# picoAvaR7.net
KiCad netlist of a schematic drawn in EAGLE
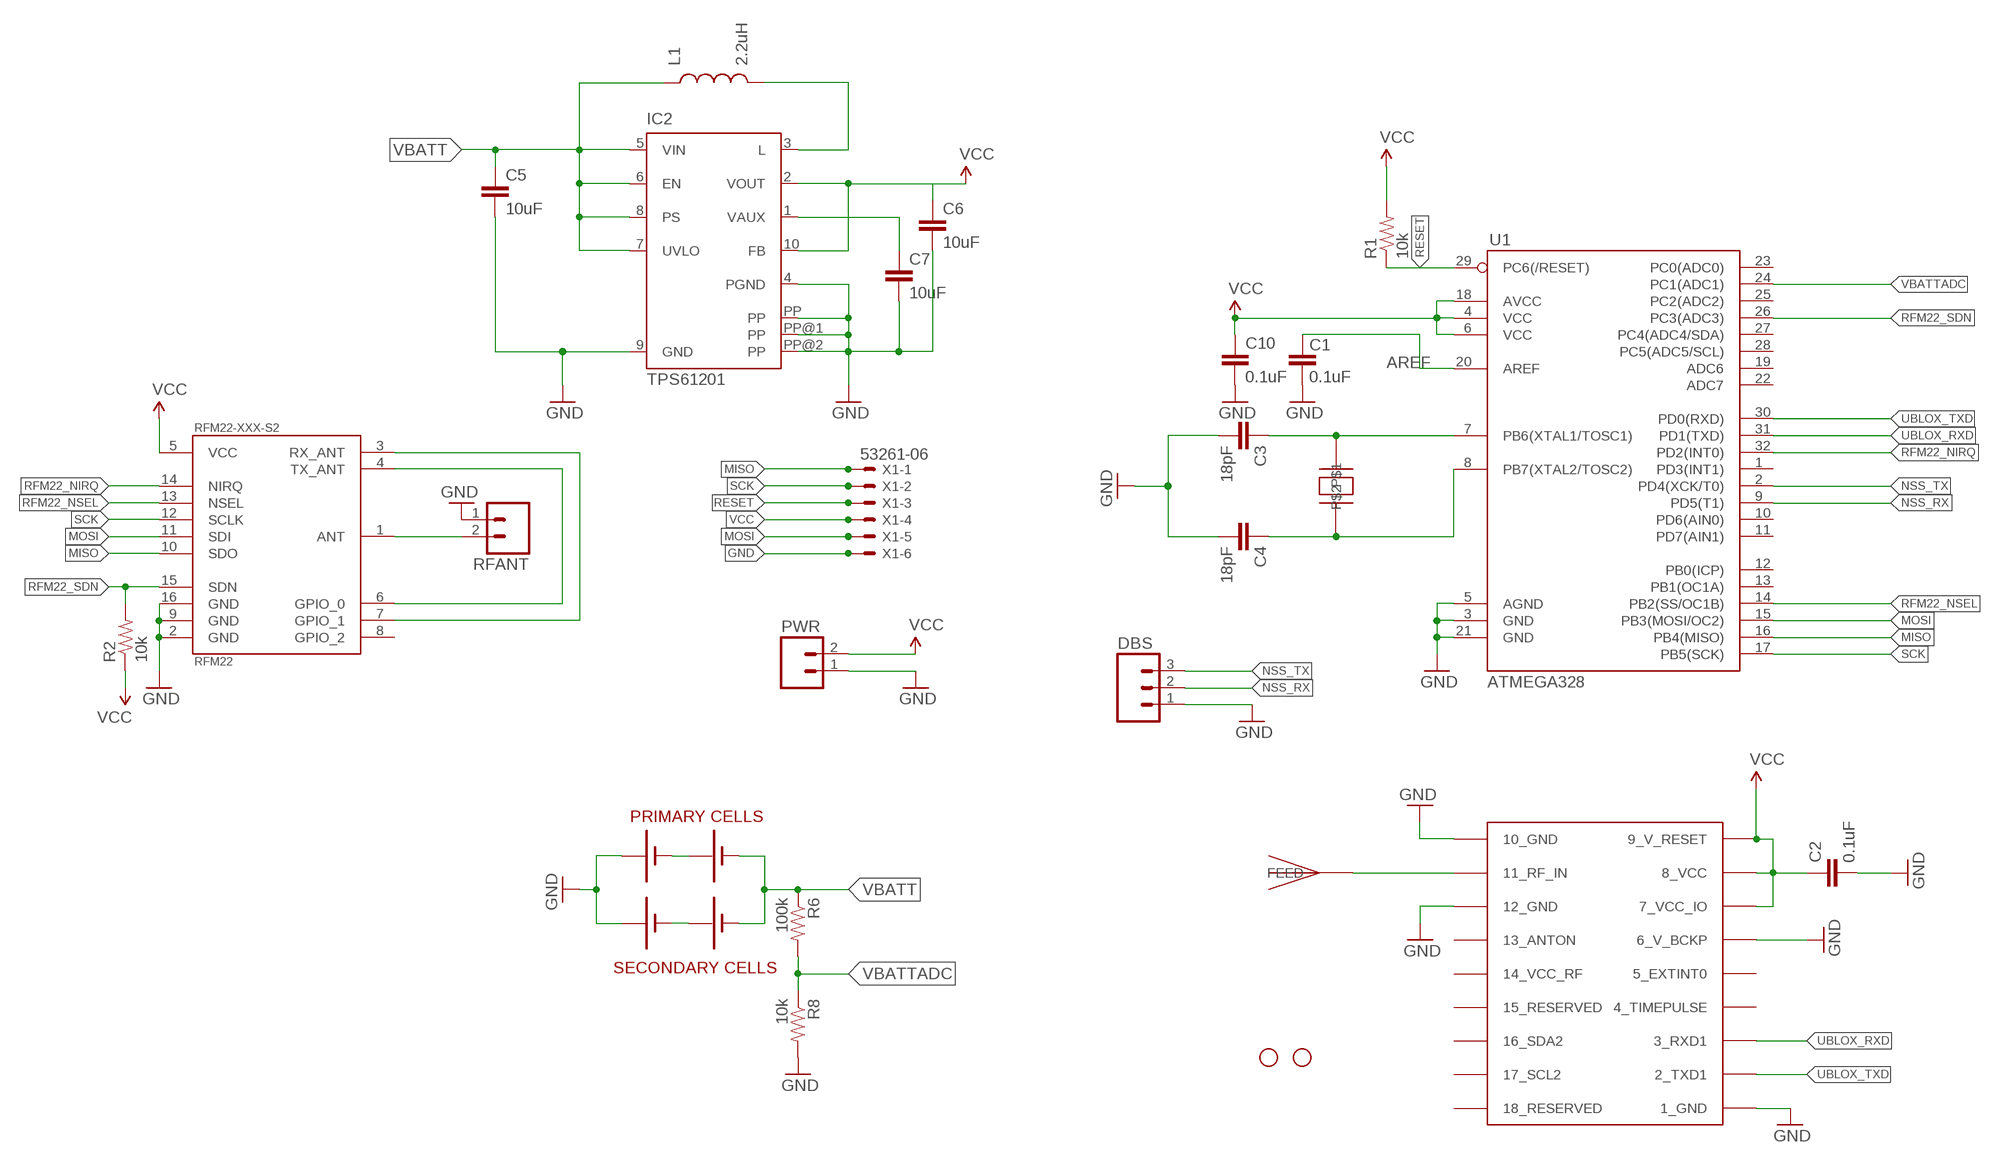
[diagram p0: schematic, sheet 1]

(export (version "E")
  (design (tool "Eeschema 10.0.6"))
  (components
    (comp (ref "C1")
      (value "0.1uF")
      (footprint "eagle-import:0402-CAP")
      (libsource (lib "eagle-import") (part "CAP0402-CAP"))
    )
    (comp (ref "C2")
      (value "0.1uF")
      (footprint "eagle-import:0402-CAP")
      (libsource (lib "eagle-import") (part "CAP0402-CAP"))
    )
    (comp (ref "C3")
      (value "18pF")
      (footprint "eagle-import:0402-CAP")
      (libsource (lib "eagle-import") (part "CAP0402-CAP"))
    )
    (comp (ref "C4")
      (value "18pF")
      (footprint "eagle-import:0402-CAP")
      (libsource (lib "eagle-import") (part "CAP0402-CAP"))
    )
    (comp (ref "C5")
      (value "10uF")
      (footprint "eagle-import:1206")
      (libsource (lib "eagle-import") (part "CAP1206"))
    )
    (comp (ref "C6")
      (value "10uF")
      (footprint "eagle-import:1206")
      (libsource (lib "eagle-import") (part "CAP1206"))
    )
    (comp (ref "C7")
      (value "10uF")
      (footprint "eagle-import:1206")
      (libsource (lib "eagle-import") (part "CAP1206"))
    )
    (comp (ref "C10")
      (value "0.1uF")
      (footprint "eagle-import:0402-CAP")
      (libsource (lib "eagle-import") (part "CAP0402-CAP"))
    )
    (comp (ref "DBS")
      (value "M03PTH")
      (footprint "eagle-import:1X03")
      (libsource (lib "eagle-import") (part "M03PTH"))
    )
    (comp (ref "IC2")
      (value "TPS61201")
      (footprint "eagle-import:S-PDSO-N10")
      (fields (field (name "MPN") "TPS61201DRCT"))
      (libsource (lib "eagle-import") (part "TPS61201"))
    )
    (comp (ref "JP1")
      (value "STAND-OFF")
      (footprint "eagle-import:STAND-OFF")
      (libsource (lib "eagle-import") (part "STAND-OFF"))
    )
    (comp (ref "JP2")
      (value "STAND-OFF")
      (footprint "eagle-import:STAND-OFF")
      (libsource (lib "eagle-import") (part "STAND-OFF"))
    )
    (comp (ref "L1")
      (value "2.2uH")
      (footprint "eagle-import:ELLVGG_INDUCTOR")
      (libsource (lib "eagle-import") (part "ELLVGG_INDUCTOR"))
    )
    (comp (ref "PRIMARYCELL1")
      (value "KEYSTONE-82-AAA-BATTERY-HOLDER")
      (footprint "eagle-import:KEYSTONE-82-AAA-BATTERY")
      (libsource (lib "eagle-import") (part "KEYSTONE-82-AAA-BATTERY-HOLDER"))
    )
    (comp (ref "PRIMARYCELL2")
      (value "KEYSTONE-82-AAA-BATTERY-HOLDER")
      (footprint "eagle-import:KEYSTONE-82-AAA-BATTERY")
      (libsource (lib "eagle-import") (part "KEYSTONE-82-AAA-BATTERY-HOLDER"))
    )
    (comp (ref "PWR")
      (value "M02PTH")
      (footprint "eagle-import:1X02")
      (libsource (lib "eagle-import") (part "M02PTH"))
    )
    (comp (ref "R1")
      (value "10k")
      (footprint "eagle-import:0402-RES")
      (libsource (lib "eagle-import") (part "RESISTOR0402-RES"))
    )
    (comp (ref "R2")
      (value "10k")
      (footprint "eagle-import:0402-RES")
      (libsource (lib "eagle-import") (part "RESISTOR0402-RES"))
    )
    (comp (ref "R6")
      (value "100k")
      (footprint "eagle-import:0402-RES")
      (libsource (lib "eagle-import") (part "RESISTOR0402-RES"))
    )
    (comp (ref "R8")
      (value "10k")
      (footprint "eagle-import:0402-RES")
      (libsource (lib "eagle-import") (part "RESISTOR0402-RES"))
    )
    (comp (ref "RFANT")
      (value "M02PTH")
      (footprint "eagle-import:1X02")
      (libsource (lib "eagle-import") (part "M02PTH"))
    )
    (comp (ref "RFM22-XXX-S2")
      (value "RFM22")
      (footprint "eagle-import:RFM22-XXX-S2")
      (libsource (lib "eagle-import") (part "RFM22"))
    )
    (comp (ref "SECONDARYCELL1")
      (value "KEYSTONE-82-AAA-BATTERY-HOLDER")
      (footprint "eagle-import:KEYSTONE-82-AAA-BATTERY")
      (libsource (lib "eagle-import") (part "KEYSTONE-82-AAA-BATTERY-HOLDER"))
    )
    (comp (ref "SECONDARYCELL2")
      (value "KEYSTONE-82-AAA-BATTERY-HOLDER")
      (footprint "eagle-import:KEYSTONE-82-AAA-BATTERY")
      (libsource (lib "eagle-import") (part "KEYSTONE-82-AAA-BATTERY-HOLDER"))
    )
    (comp (ref "U$1")
      (value "UBLOX_MAX-6")
      (footprint "eagle-import:UBLOX_MAX-6")
      (libsource (lib "eagle-import") (part "UBLOX_MAX-6"))
    )
    (comp (ref "U$2")
      (value "ABRACON_ABM3_CRYSTAL")
      (footprint "eagle-import:ABRACON_ABM3_CRYSTAL")
      (libsource (lib "eagle-import") (part "ABRACON_ABM3_CRYSTAL"))
    )
    (comp (ref "U$3")
      (value "JTI_ANTENNA-1575AT43A40")
      (footprint "eagle-import:JTI_ANTENNA-1575AT43A40")
      (libsource (lib "eagle-import") (part "JTI_ANTENNA-1575AT43A40"))
    )
    (comp (ref "U1")
      (value "ATMEGA328")
      (footprint "eagle-import:TQFP32-08")
      (libsource (lib "eagle-import") (part "ATMEGA168"))
    )
    (comp (ref "X1")
      (value "53261-06")
      (footprint "eagle-import:53261-06")
      (libsource (lib "eagle-import") (part "53?-06261"))
    )
  )
  (nets
    (net (code "1") (name "/AREF") (class "Default")
      (node (ref "C1") (pin "2") (pinfunction "2_2") (pintype "passive"))
      (node (ref "U1") (pin "20") (pinfunction "AREF_20") (pintype "bidirectional"))
    )
    (net (code "2") (name "GND") (class "Default")
      (node (ref "C1") (pin "1") (pinfunction "1_1") (pintype "passive"))
      (node (ref "C10") (pin "2") (pinfunction "2_2") (pintype "passive"))
      (node (ref "C2") (pin "2") (pinfunction "2_2") (pintype "passive"))
      (node (ref "C3") (pin "2") (pinfunction "2_2") (pintype "passive"))
      (node (ref "C4") (pin "2") (pinfunction "2_2") (pintype "passive"))
      (node (ref "C5") (pin "2") (pinfunction "2_2") (pintype "passive"))
      (node (ref "C6") (pin "2") (pinfunction "2_2") (pintype "passive"))
      (node (ref "C7") (pin "2") (pinfunction "2_2") (pintype "passive"))
      (node (ref "DBS") (pin "1") (pinfunction "1_1") (pintype "passive"))
      (node (ref "IC2") (pin "4") (pinfunction "PGND_4") (pintype "power_in"))
      (node (ref "IC2") (pin "9") (pinfunction "GND_9") (pintype "power_in"))
      (node (ref "IC2") (pin "PP") (pinfunction "PP_PP") (pintype "power_in"))
      (node (ref "IC2") (pin "PP@1") (pinfunction "PP_PP@1") (pintype "power_in"))
      (node (ref "IC2") (pin "PP@2") (pinfunction "PP_PP@2") (pintype "power_in"))
      (node (ref "PRIMARYCELL1") (pin "VBATT") (pinfunction "+_VBATT") (pintype "power_in"))
      (node (ref "PRIMARYCELL1") (pin "VBATT1") (pinfunction "+_VBATT1") (pintype "power_in"))
      (node (ref "PWR") (pin "1") (pinfunction "1_1") (pintype "passive"))
      (node (ref "R8") (pin "2") (pinfunction "2_2") (pintype "passive"))
      (node (ref "RFANT") (pin "1") (pinfunction "1_1") (pintype "passive"))
      (node (ref "RFM22-XXX-S2") (pin "16") (pinfunction "GND_16") (pintype "power_in"))
      (node (ref "RFM22-XXX-S2") (pin "2") (pinfunction "GND_2") (pintype "power_in"))
      (node (ref "RFM22-XXX-S2") (pin "9") (pinfunction "GND_9") (pintype "power_in"))
      (node (ref "SECONDARYCELL1") (pin "VBATT") (pinfunction "+_VBATT") (pintype "power_in"))
      (node (ref "SECONDARYCELL1") (pin "VBATT1") (pinfunction "+_VBATT1") (pintype "power_in"))
      (node (ref "U$1") (pin "10_GND") (pinfunction "10_GND_10_GND") (pintype "bidirectional"))
      (node (ref "U$1") (pin "12_GND") (pinfunction "12_GND_12_GND") (pintype "bidirectional"))
      (node (ref "U$1") (pin "1_GND") (pinfunction "1_GND_1_GND") (pintype "bidirectional"))
      (node (ref "U$1") (pin "6_V_BCKP") (pinfunction "6_V_BCKP_6_V_BCKP") (pintype "bidirectional"))
      (node (ref "U1") (pin "21") (pinfunction "GND_21") (pintype "bidirectional"))
      (node (ref "U1") (pin "3") (pinfunction "GND_3") (pintype "bidirectional"))
      (node (ref "U1") (pin "5") (pinfunction "AGND_5") (pintype "bidirectional"))
      (node (ref "X1") (pin "6") (pinfunction "S_6") (pintype "passive"))
    )
    (net (code "3") (name "MISO") (class "Default")
      (node (ref "RFM22-XXX-S2") (pin "10") (pinfunction "SDO_10") (pintype "output"))
      (node (ref "U1") (pin "16") (pinfunction "PB4(MISO)_16") (pintype "bidirectional"))
      (node (ref "X1") (pin "1") (pinfunction "S_1") (pintype "passive"))
    )
    (net (code "4") (name "MOSI") (class "Default")
      (node (ref "RFM22-XXX-S2") (pin "11") (pinfunction "SDI_11") (pintype "input"))
      (node (ref "U1") (pin "15") (pinfunction "PB3(MOSI/OC2)_15") (pintype "bidirectional"))
      (node (ref "X1") (pin "5") (pinfunction "S_5") (pintype "passive"))
    )
    (net (code "5") (name "NSS_RX") (class "Default")
      (node (ref "DBS") (pin "2") (pinfunction "2_2") (pintype "passive"))
      (node (ref "U1") (pin "9") (pinfunction "PD5(T1)_9") (pintype "bidirectional"))
    )
    (net (code "6") (name "NSS_TX") (class "Default")
      (node (ref "DBS") (pin "3") (pinfunction "3_3") (pintype "passive"))
      (node (ref "U1") (pin "2") (pinfunction "PD4(XCK/T0)_2") (pintype "bidirectional"))
    )
    (net (code "7") (name "Net-(IC2-L)") (class "Default")
      (node (ref "IC2") (pin "3") (pinfunction "L_3") (pintype "input"))
      (node (ref "L1") (pin "P$2") (pinfunction "2_P$2") (pintype "passive"))
    )
    (net (code "8") (name "Net-(IC2-VAUX)") (class "Default")
      (node (ref "C7") (pin "1") (pinfunction "1_1") (pintype "passive"))
      (node (ref "IC2") (pin "1") (pinfunction "VAUX_1") (pintype "bidirectional"))
    )
    (net (code "9") (name "Net-(PRIMARYCELL1---PadGND)") (class "Default")
      (node (ref "PRIMARYCELL1") (pin "GND") (pinfunction "-_GND") (pintype "power_in"))
      (node (ref "PRIMARYCELL1") (pin "GND2") (pinfunction "-_GND2") (pintype "power_in"))
      (node (ref "PRIMARYCELL2") (pin "VBATT") (pinfunction "+_VBATT") (pintype "power_in"))
      (node (ref "PRIMARYCELL2") (pin "VBATT1") (pinfunction "+_VBATT1") (pintype "power_in"))
    )
    (net (code "10") (name "Net-(RFM22-XXX-S2-ANT)") (class "Default")
      (node (ref "RFANT") (pin "2") (pinfunction "2_2") (pintype "passive"))
      (node (ref "RFM22-XXX-S2") (pin "1") (pinfunction "ANT_1") (pintype "bidirectional"))
    )
    (net (code "11") (name "Net-(RFM22-XXX-S2-GPIO_0)") (class "Default")
      (node (ref "RFM22-XXX-S2") (pin "4") (pinfunction "TX_ANT_4") (pintype "input"))
      (node (ref "RFM22-XXX-S2") (pin "6") (pinfunction "GPIO_0_6") (pintype "bidirectional"))
    )
    (net (code "12") (name "Net-(RFM22-XXX-S2-GPIO_1)") (class "Default")
      (node (ref "RFM22-XXX-S2") (pin "3") (pinfunction "RX_ANT_3") (pintype "input"))
      (node (ref "RFM22-XXX-S2") (pin "7") (pinfunction "GPIO_1_7") (pintype "bidirectional"))
    )
    (net (code "13") (name "Net-(SECONDARYCELL1---PadGND)") (class "Default")
      (node (ref "SECONDARYCELL1") (pin "GND") (pinfunction "-_GND") (pintype "power_in"))
      (node (ref "SECONDARYCELL1") (pin "GND2") (pinfunction "-_GND2") (pintype "power_in"))
      (node (ref "SECONDARYCELL2") (pin "VBATT") (pinfunction "+_VBATT") (pintype "power_in"))
      (node (ref "SECONDARYCELL2") (pin "VBATT1") (pinfunction "+_VBATT1") (pintype "power_in"))
    )
    (net (code "14") (name "Net-(U$1-Pad11_RF_IN)") (class "Default")
      (node (ref "U$1") (pin "11_RF_IN") (pinfunction "11_RF_IN_11_RF_IN") (pintype "bidirectional"))
      (node (ref "U$3") (pin "FEED") (pinfunction "FEED_FEED") (pintype "bidirectional"))
    )
    (net (code "15") (name "Net-(U1-PB6(XTAL1{slash}TOSC1))") (class "Default")
      (node (ref "C3") (pin "1") (pinfunction "1_1") (pintype "passive"))
      (node (ref "U$2") (pin "P$2") (pinfunction "P$2_P$2") (pintype "bidirectional"))
      (node (ref "U1") (pin "7") (pinfunction "PB6(XTAL1/TOSC1)_7") (pintype "bidirectional"))
    )
    (net (code "16") (name "Net-(U1-PB7(XTAL2{slash}TOSC2))") (class "Default")
      (node (ref "C4") (pin "1") (pinfunction "1_1") (pintype "passive"))
      (node (ref "U$2") (pin "P$1") (pinfunction "P$1_P$1") (pintype "bidirectional"))
      (node (ref "U1") (pin "8") (pinfunction "PB7(XTAL2/TOSC2)_8") (pintype "bidirectional"))
    )
    (net (code "17") (name "RESET") (class "Default")
      (node (ref "R1") (pin "1") (pinfunction "1_1") (pintype "passive"))
      (node (ref "U1") (pin "29") (pinfunction "PC6(/RESET)_29") (pintype "bidirectional"))
      (node (ref "X1") (pin "3") (pinfunction "S_3") (pintype "passive"))
    )
    (net (code "18") (name "RFM22_NIRQ") (class "Default")
      (node (ref "RFM22-XXX-S2") (pin "14") (pinfunction "NIRQ_14") (pintype "output"))
      (node (ref "U1") (pin "32") (pinfunction "PD2(INT0)_32") (pintype "bidirectional"))
    )
    (net (code "19") (name "RFM22_NSEL") (class "Default")
      (node (ref "RFM22-XXX-S2") (pin "13") (pinfunction "NSEL_13") (pintype "input"))
      (node (ref "U1") (pin "14") (pinfunction "PB2(SS/OC1B)_14") (pintype "bidirectional"))
    )
    (net (code "20") (name "RFM22_SDN") (class "Default")
      (node (ref "R2") (pin "2") (pinfunction "2_2") (pintype "passive"))
      (node (ref "RFM22-XXX-S2") (pin "15") (pinfunction "SDN_15") (pintype "input"))
      (node (ref "U1") (pin "26") (pinfunction "PC3(ADC3)_26") (pintype "bidirectional"))
    )
    (net (code "21") (name "SCK") (class "Default")
      (node (ref "RFM22-XXX-S2") (pin "12") (pinfunction "SCLK_12") (pintype "input"))
      (node (ref "U1") (pin "17") (pinfunction "PB5(SCK)_17") (pintype "bidirectional"))
      (node (ref "X1") (pin "2") (pinfunction "S_2") (pintype "passive"))
    )
    (net (code "22") (name "UBLOX_RXD") (class "Default")
      (node (ref "U$1") (pin "3_RXD1") (pinfunction "3_RXD1_3_RXD1") (pintype "bidirectional"))
      (node (ref "U1") (pin "31") (pinfunction "PD1(TXD)_31") (pintype "bidirectional"))
    )
    (net (code "23") (name "UBLOX_TXD") (class "Default")
      (node (ref "U$1") (pin "2_TXD1") (pinfunction "2_TXD1_2_TXD1") (pintype "bidirectional"))
      (node (ref "U1") (pin "30") (pinfunction "PD0(RXD)_30") (pintype "bidirectional"))
    )
    (net (code "24") (name "VBATT") (class "Default")
      (node (ref "C5") (pin "1") (pinfunction "1_1") (pintype "passive"))
      (node (ref "IC2") (pin "5") (pinfunction "VIN_5") (pintype "input"))
      (node (ref "IC2") (pin "6") (pinfunction "EN_6") (pintype "input"))
      (node (ref "IC2") (pin "7") (pinfunction "UVLO_7") (pintype "input"))
      (node (ref "IC2") (pin "8") (pinfunction "PS_8") (pintype "input"))
      (node (ref "L1") (pin "P$1") (pinfunction "1_P$1") (pintype "passive"))
      (node (ref "PRIMARYCELL2") (pin "GND") (pinfunction "-_GND") (pintype "power_in"))
      (node (ref "PRIMARYCELL2") (pin "GND2") (pinfunction "-_GND2") (pintype "power_in"))
      (node (ref "R6") (pin "1") (pinfunction "1_1") (pintype "passive"))
      (node (ref "SECONDARYCELL2") (pin "GND") (pinfunction "-_GND") (pintype "power_in"))
      (node (ref "SECONDARYCELL2") (pin "GND2") (pinfunction "-_GND2") (pintype "power_in"))
    )
    (net (code "25") (name "VBATTADC") (class "Default")
      (node (ref "R6") (pin "2") (pinfunction "2_2") (pintype "passive"))
      (node (ref "R8") (pin "1") (pinfunction "1_1") (pintype "passive"))
      (node (ref "U1") (pin "24") (pinfunction "PC1(ADC1)_24") (pintype "bidirectional"))
    )
    (net (code "26") (name "VCC") (class "Default")
      (node (ref "C10") (pin "1") (pinfunction "1_1") (pintype "passive"))
      (node (ref "C2") (pin "1") (pinfunction "1_1") (pintype "passive"))
      (node (ref "C6") (pin "1") (pinfunction "1_1") (pintype "passive"))
      (node (ref "IC2") (pin "10") (pinfunction "FB_10") (pintype "input"))
      (node (ref "IC2") (pin "2") (pinfunction "VOUT_2") (pintype "passive"))
      (node (ref "PWR") (pin "2") (pinfunction "2_2") (pintype "passive"))
      (node (ref "R1") (pin "2") (pinfunction "2_2") (pintype "passive"))
      (node (ref "R2") (pin "1") (pinfunction "1_1") (pintype "passive"))
      (node (ref "RFM22-XXX-S2") (pin "5") (pinfunction "VCC_5") (pintype "bidirectional"))
      (node (ref "U$1") (pin "7_VCC_IO") (pinfunction "7_VCC_IO_7_VCC_IO") (pintype "bidirectional"))
      (node (ref "U$1") (pin "8_VCC") (pinfunction "8_VCC_8_VCC") (pintype "bidirectional"))
      (node (ref "U$1") (pin "9_V_RESET") (pinfunction "9_V_RESET_9_V_RESET") (pintype "bidirectional"))
      (node (ref "U1") (pin "18") (pinfunction "AVCC_18") (pintype "bidirectional"))
      (node (ref "U1") (pin "4") (pinfunction "VCC_4") (pintype "bidirectional"))
      (node (ref "U1") (pin "6") (pinfunction "VCC_6") (pintype "bidirectional"))
      (node (ref "X1") (pin "4") (pinfunction "S_4") (pintype "passive"))
    )
    (net (code "27") (name "unconnected-(RFM22-XXX-S2-GPIO_2-Pad8)") (class "Default")
      (node (ref "RFM22-XXX-S2") (pin "8") (pinfunction "GPIO_2_8") (pintype "bidirectional"))
    )
    (net (code "28") (name "unconnected-(U$1-Pad4_TIMEPULSE)") (class "Default")
      (node (ref "U$1") (pin "4_TIMEPULSE") (pinfunction "4_TIMEPULSE_4_TIMEPULSE") (pintype "bidirectional"))
    )
    (net (code "29") (name "unconnected-(U$1-Pad5_EXTINT0)") (class "Default")
      (node (ref "U$1") (pin "5_EXTINT0") (pinfunction "5_EXTINT0_5_EXTINT0") (pintype "bidirectional"))
    )
    (net (code "30") (name "unconnected-(U$1-Pad13_ANTON)") (class "Default")
      (node (ref "U$1") (pin "13_ANTON") (pinfunction "13_ANTON_13_ANTON") (pintype "bidirectional"))
    )
    (net (code "31") (name "unconnected-(U$1-Pad14_VCC_RF)") (class "Default")
      (node (ref "U$1") (pin "14_VCC_RF") (pinfunction "14_VCC_RF_14_VCC_RF") (pintype "bidirectional"))
    )
    (net (code "32") (name "unconnected-(U$1-Pad15_RESERVED)") (class "Default")
      (node (ref "U$1") (pin "15_RESERVED") (pinfunction "15_RESERVED_15_RESERVED") (pintype "bidirectional"))
    )
    (net (code "33") (name "unconnected-(U$1-Pad16_SDA2)") (class "Default")
      (node (ref "U$1") (pin "16_SDA2") (pinfunction "16_SDA2_16_SDA2") (pintype "bidirectional"))
    )
    (net (code "34") (name "unconnected-(U$1-Pad17_SCL2)") (class "Default")
      (node (ref "U$1") (pin "17_SCL2") (pinfunction "17_SCL2_17_SCL2") (pintype "bidirectional"))
    )
    (net (code "35") (name "unconnected-(U$1-Pad18_RESERVED)") (class "Default")
      (node (ref "U$1") (pin "18_RESERVED") (pinfunction "18_RESERVED_18_RESERVED") (pintype "bidirectional"))
    )
    (net (code "36") (name "unconnected-(U1-ADC6-Pad19)") (class "Default")
      (node (ref "U1") (pin "19") (pinfunction "ADC6_19") (pintype "bidirectional"))
    )
    (net (code "37") (name "unconnected-(U1-ADC7-Pad22)") (class "Default")
      (node (ref "U1") (pin "22") (pinfunction "ADC7_22") (pintype "bidirectional"))
    )
    (net (code "38") (name "unconnected-(U1-PB0(ICP)-Pad12)") (class "Default")
      (node (ref "U1") (pin "12") (pinfunction "PB0(ICP)_12") (pintype "bidirectional"))
    )
    (net (code "39") (name "unconnected-(U1-PB1(OC1A)-Pad13)") (class "Default")
      (node (ref "U1") (pin "13") (pinfunction "PB1(OC1A)_13") (pintype "bidirectional"))
    )
    (net (code "40") (name "unconnected-(U1-PC0(ADC0)-Pad23)") (class "Default")
      (node (ref "U1") (pin "23") (pinfunction "PC0(ADC0)_23") (pintype "bidirectional"))
    )
    (net (code "41") (name "unconnected-(U1-PC2(ADC2)-Pad25)") (class "Default")
      (node (ref "U1") (pin "25") (pinfunction "PC2(ADC2)_25") (pintype "bidirectional"))
    )
    (net (code "42") (name "unconnected-(U1-PC4(ADC4{slash}SDA)-Pad27)") (class "Default")
      (node (ref "U1") (pin "27") (pinfunction "PC4(ADC4/SDA)_27") (pintype "bidirectional"))
    )
    (net (code "43") (name "unconnected-(U1-PC5(ADC5{slash}SCL)-Pad28)") (class "Default")
      (node (ref "U1") (pin "28") (pinfunction "PC5(ADC5/SCL)_28") (pintype "bidirectional"))
    )
    (net (code "44") (name "unconnected-(U1-PD3(INT1)-Pad1)") (class "Default")
      (node (ref "U1") (pin "1") (pinfunction "PD3(INT1)_1") (pintype "bidirectional"))
    )
    (net (code "45") (name "unconnected-(U1-PD6(AIN0)-Pad10)") (class "Default")
      (node (ref "U1") (pin "10") (pinfunction "PD6(AIN0)_10") (pintype "bidirectional"))
    )
    (net (code "46") (name "unconnected-(U1-PD7(AIN1)-Pad11)") (class "Default")
      (node (ref "U1") (pin "11") (pinfunction "PD7(AIN1)_11") (pintype "bidirectional"))
    )
  )
)
